# posture_corrector_schematic.net
KiCad netlist of a schematic drawn in Altium Designer
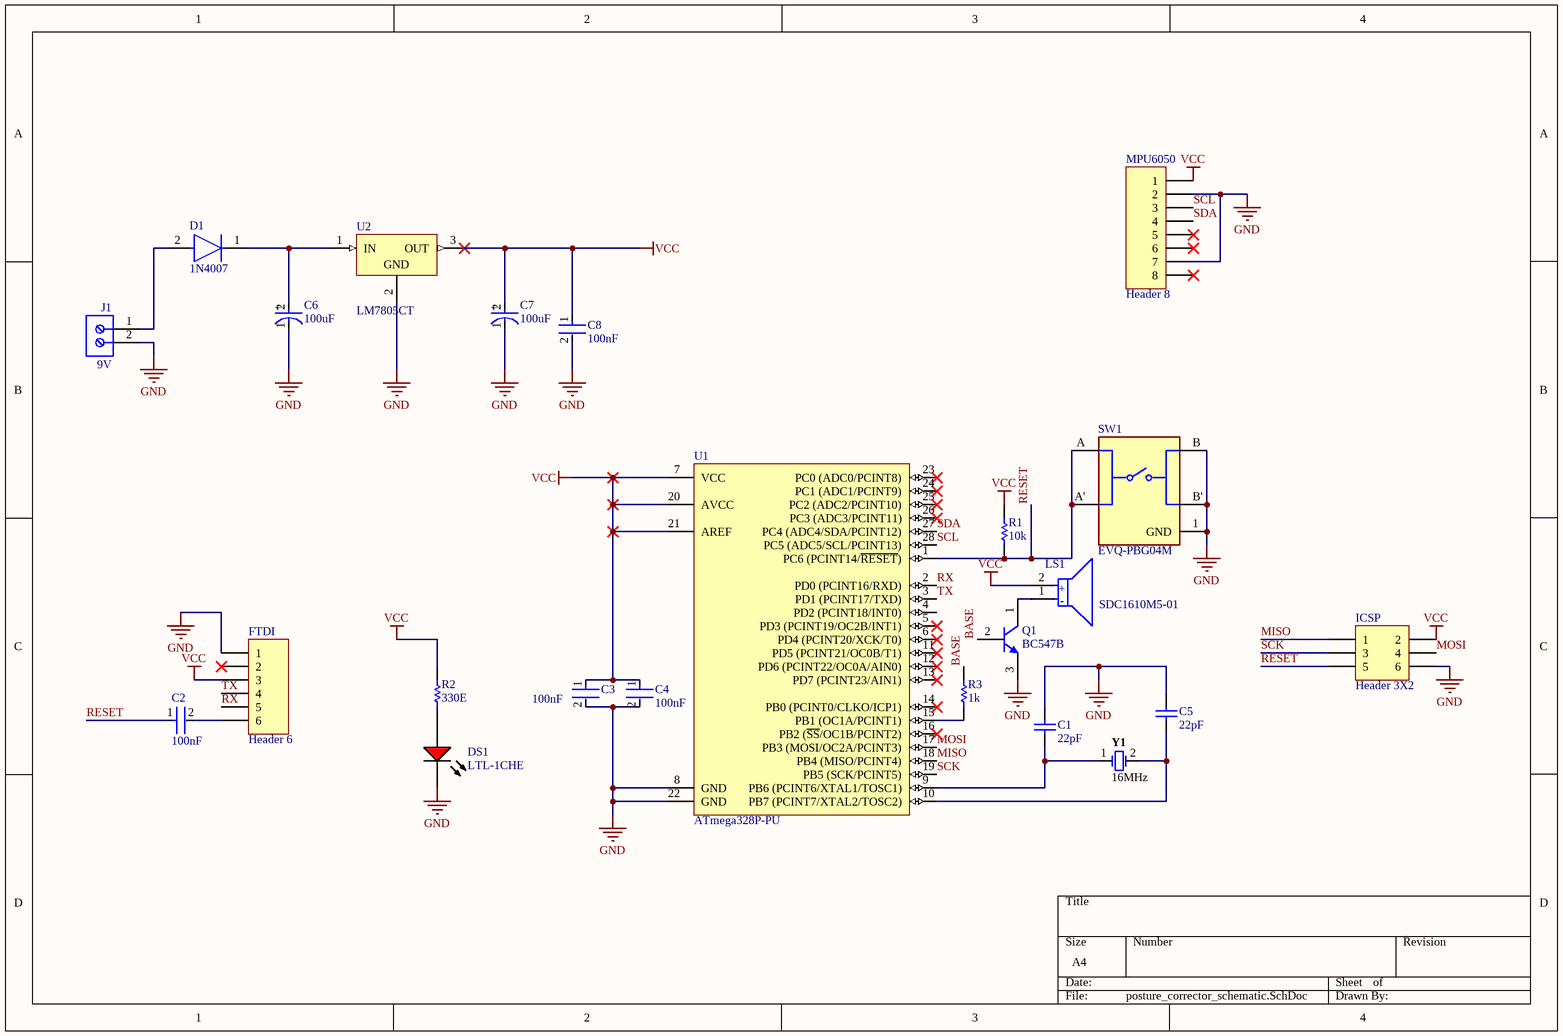
[diagram p0: posture_corrector_schematic.SchDoc]

(export (version "E")
  (design (tool "Eeschema 10.0.6"))
  (components
    (comp (ref "C1")
      (value "22pF")
      (footprint "KEMT-C315-THT-2")
      (description "Capacitor, Ceramic, 22 pF, +/-10 %, 100 V, -55 to 125 degC, 2-Pin THD, RoHS, Bulk")
      (libsource (lib "Altium Content Vault") (part "CAP-NP-2"))
    )
    (comp (ref "C2")
      (value "100nF")
      (footprint "FP-RCE1A2-MFG")
      (description "Cap Ceramic 100nF 100V X7R ±10% Radial 2.5mm +125°C Automotive Ammo Pack")
      (fields (field (name "TOLERANCE") "10%"))
      (libsource (lib "Altium Content Vault") (part "02cd4be3c70576c341d710602a673aa"))
    )
    (comp (ref "C3")
      (value "100nF")
      (footprint "FP-RCE1K1-2_5-MFG")
      (description "Cap Ceramic Monolithic 100nF 100V 10% Thru-Hole Bulk")
      (fields (field (name "TOLERANCE") "10%"))
      (libsource (lib "Altium Content Vault") (part "02cd4be3c70576c341d710602a673aa"))
    )
    (comp (ref "C4")
      (value "100nF")
      (footprint "FP-RCE1K1-2_5-MFG")
      (description "Cap Ceramic Monolithic 100nF 100V 10% Thru-Hole Bulk")
      (fields (field (name "TOLERANCE") "10%"))
      (libsource (lib "Altium Content Vault") (part "02cd4be3c70576c341d710602a673aa"))
    )
    (comp (ref "C5")
      (value "22pF")
      (footprint "KEMT-C315-THT-2")
      (description "Capacitor, Ceramic, 22 pF, +/-10 %, 100 V, -55 to 125 degC, 2-Pin THD, RoHS, Bulk")
      (libsource (lib "Altium Content Vault") (part "CAP-NP-2"))
    )
    (comp (ref "C6")
      (value "100uF")
      (footprint "FP-RAD-TH-D_6_3_0_5-L_11-MFG")
      (description "Aluminum Electrolytic Capacitors (Radial Lead Type) 2.2uF ±20% 250V")
      (fields (field (name "TOLERANCE") "20%"))
      (libsource (lib "Altium Content Vault") (part "203bc49f2ac43e59fd269a8c329ed05"))
    )
    (comp (ref "C7")
      (value "100uF")
      (footprint "FP-RAD-TH-D_6_3_0_5-L_11-MFG")
      (description "Aluminum Electrolytic Capacitors (Radial Lead Type) 2.2uF ±20% 250V")
      (fields (field (name "TOLERANCE") "20%"))
      (libsource (lib "Altium Content Vault") (part "203bc49f2ac43e59fd269a8c329ed05"))
    )
    (comp (ref "C8")
      (value "100nF")
      (footprint "FP-RCE1K1-2_5-MFG")
      (description "Cap Ceramic Monolithic 100nF 100V 10% Thru-Hole Bulk")
      (fields (field (name "TOLERANCE") "10%"))
      (libsource (lib "Altium Content Vault") (part "02cd4be3c70576c341d710602a673aa"))
    )
    (comp (ref "D1")
      (value "1N4007")
      (footprint "FP-1N4007E-E3-54-MFG")
      (description "DIODE GEN PURP 1KV 1A DO204AL")
      (libsource (lib "Altium Content Vault") (part "d7152d700b627762746794eb795d46e"))
    )
    (comp (ref "DS1")
      (value "LTL-1CHE")
      (footprint "INDPR60-254-520X380X650")
      (description "Radial LED, 12.6 mcd, 20 mA, 2 V, -55 to 100 degC, 2-Pin THD, RoHS, Bulk")
      (fields (field (name "TOLERANCE") "20%"))
      (libsource (lib "Altium Content Vault") (part "LED-RED-AK-2"))
    )
    (comp (ref "FTDI")
      (value "Header 6")
      (footprint "HDR1X6")
      (description "Header, 6-Pin")
      (fields (field (name "PUBLISHER") "Altium Limited"))
      (libsource (lib "Miscellaneous Connectors") (part "Header 6"))
    )
    (comp (ref "ICSP")
      (value "Header 3X2")
      (footprint "HDR2X3")
      (description "Header, 3-Pin, Dual row")
      (fields (field (name "PUBLISHER") "Altium Limited"))
      (libsource (lib "Miscellaneous Connectors") (part "Header 3X2"))
    )
    (comp (ref "J1")
      (value "9V")
      (footprint "691211720002")
      (description "211 Series 5MM Pitch Straight, Pcb Terminal Block, Through Hole, 2 Way")
      (fields (field (name "VOLTAGE") "300V"))
      (libsource (lib "Altium Content Vault") (part "TBL - 1R - 02P - Screw"))
    )
    (comp (ref "LS1")
      (value "SDC1610M5-01")
      (footprint "FP-SDC1610M5-01-MFG")
      (description "AUDIO MAGNETIC INDICATOR 4-8V TH")
      (libsource (lib "Altium Content Vault") (part "f7ec632b6fea80cbef86dc3340f200c"))
    )
    (comp (ref "MPU6050")
      (value "Header 8")
      (footprint "HDR1X8")
      (description "Header, 8-Pin")
      (fields (field (name "PUBLISHER") "Altium Limited"))
      (libsource (lib "Miscellaneous Connectors") (part "Header 8"))
    )
    (comp (ref "Q1")
      (value "BC547B")
      (footprint "ONSC-TO-92-3-29-11")
      (description "Amplifier Transistor, NPN Silicon, 3-Pin TO-92, Bulk Box")
      (fields (field (name "MANUFACTURER") "On Semiconductor"))
      (libsource (lib "Altium Content Vault") (part "ONSC-NPN-C1B2E3-3"))
    )
    (comp (ref "R1")
      (value "10k")
      (footprint "AXIAL-0.3")
      (description "Resistor")
      (fields (field (name "PUBLISHER") "Altium Limited"))
      (libsource (lib "Miscellaneous Devices") (part "Res1"))
    )
    (comp (ref "R2")
      (value "330E")
      (footprint "AXIAL-0.3")
      (description "Resistor")
      (fields (field (name "PUBLISHER") "Altium Limited"))
      (libsource (lib "Miscellaneous Devices") (part "Res1"))
    )
    (comp (ref "R3")
      (value "1k")
      (footprint "AXIAL-0.3")
      (description "Resistor")
      (fields (field (name "PUBLISHER") "Altium Limited"))
      (libsource (lib "Miscellaneous Devices") (part "Res1"))
    )
    (comp (ref "SW1")
      (value "EVQ-PBG04M")
      (footprint "FP-EVQ-PBG04M-MFG")
      (description "SWITCH TACTILE SPST-NO 0.02A 15V")
      (libsource (lib "Altium Content Vault") (part "2124b69ba03152b6ee5348f5a6e82e9"))
    )
    (comp (ref "U1")
      (value "ATmega328P-PU")
      (footprint "28P3")
      (libsource (lib "Altium Content Vault") (part "MC-8B-ATM48-IL28"))
    )
    (comp (ref "U2")
      (value "LM7805CT")
      (footprint "FAIR-TO-220-3")
      (description "Positive Voltage Regulator, 5 V, 1 A, -40 to 125 degC, 3-Pin TO-220, RoHS, Tube")
      (fields (field (name "MANUFACTURER") "FairchildSemiconductor"))
      (libsource (lib "Altium Content Vault") (part "FAIR-LM7805CT-TO220-3"))
    )
    (comp (ref "Y1")
      (value "16MHz")
      (footprint "FOX-FOXSLF160-20")
      (description "Resistance Weld Thru-Hole Crystal, 16 MHz, -20 to 70 degC, 2-Pin THD, RoHS, Bulk")
      (fields (field (name "TOLERANCE") "1%"))
      (libsource (lib "Altium Content Vault") (part "XTAL-1-2-2"))
    )
  )
  (nets
    (net (code "1") (name "/BASE") (class "Default")
      (node (ref "Q1") (pin "2") (pinfunction "B_2") (pintype "passive"))
      (node (ref "R3") (pin "2") (pinfunction "2_2") (pintype "passive"))
    )
    (net (code "2") (name "/MISO") (class "Default")
      (node (ref "ICSP") (pin "1") (pinfunction "1_1") (pintype "passive"))
      (node (ref "U1") (pin "18") (pinfunction "PB4_(MISO/PCINT4)_18") (pintype "bidirectional"))
    )
    (net (code "3") (name "/MOSI") (class "Default")
      (node (ref "ICSP") (pin "4") (pinfunction "4_4") (pintype "passive"))
      (node (ref "U1") (pin "17") (pinfunction "PB3_(MOSI/OC2A/PCINT3)_17") (pintype "bidirectional"))
    )
    (net (code "4") (name "/RESET") (class "Default")
      (node (ref "C2") (pin "1") (pinfunction "1_1") (pintype "passive"))
      (node (ref "ICSP") (pin "5") (pinfunction "5_5") (pintype "passive"))
      (node (ref "R1") (pin "1") (pinfunction "1_1") (pintype "passive"))
      (node (ref "SW1") (pin "A") (pinfunction "A_A") (pintype "passive"))
      (node (ref "SW1") (pin "A'") (pinfunction "A'_A'") (pintype "passive"))
      (node (ref "U1") (pin "1") (pinfunction "PC6_(PCINT14/~{RESET})_1") (pintype "bidirectional"))
    )
    (net (code "5") (name "/RX") (class "Default")
      (node (ref "FTDI") (pin "5") (pinfunction "5_5") (pintype "passive"))
      (node (ref "U1") (pin "2") (pinfunction "PD0_(PCINT16/RXD)_2") (pintype "bidirectional"))
    )
    (net (code "6") (name "/SCK") (class "Default")
      (node (ref "ICSP") (pin "3") (pinfunction "3_3") (pintype "passive"))
      (node (ref "U1") (pin "19") (pinfunction "PB5_(SCK/PCINT5)_19") (pintype "bidirectional"))
    )
    (net (code "7") (name "/SCL") (class "Default")
      (node (ref "MPU6050") (pin "3") (pinfunction "3_3") (pintype "passive"))
      (node (ref "U1") (pin "28") (pinfunction "PC5_(ADC5/SCL/PCINT13)_28") (pintype "bidirectional"))
    )
    (net (code "8") (name "/SDA") (class "Default")
      (node (ref "MPU6050") (pin "4") (pinfunction "4_4") (pintype "passive"))
      (node (ref "U1") (pin "27") (pinfunction "PC4_(ADC4/SDA/PCINT12)_27") (pintype "bidirectional"))
    )
    (net (code "9") (name "/TX") (class "Default")
      (node (ref "FTDI") (pin "4") (pinfunction "4_4") (pintype "passive"))
      (node (ref "U1") (pin "3") (pinfunction "PD1_(PCINT17/TXD)_3") (pintype "bidirectional"))
    )
    (net (code "10") (name "GND") (class "Default")
      (node (ref "C1") (pin "2") (pinfunction "2_2") (pintype "passive"))
      (node (ref "C3") (pin "2") (pinfunction "2_2") (pintype "passive"))
      (node (ref "C4") (pin "2") (pinfunction "2_2") (pintype "passive"))
      (node (ref "C5") (pin "2") (pinfunction "2_2") (pintype "passive"))
      (node (ref "C6") (pin "1") (pinfunction "C_1") (pintype "passive"))
      (node (ref "C7") (pin "1") (pinfunction "C_1") (pintype "passive"))
      (node (ref "C8") (pin "2") (pinfunction "2_2") (pintype "passive"))
      (node (ref "DS1") (pin "2") (pinfunction "K_2") (pintype "passive"))
      (node (ref "FTDI") (pin "1") (pinfunction "1_1") (pintype "passive"))
      (node (ref "ICSP") (pin "6") (pinfunction "6_6") (pintype "passive"))
      (node (ref "J1") (pin "2") (pinfunction "2_2") (pintype "passive"))
      (node (ref "MPU6050") (pin "2") (pinfunction "2_2") (pintype "passive"))
      (node (ref "MPU6050") (pin "7") (pinfunction "7_7") (pintype "passive"))
      (node (ref "Q1") (pin "3") (pinfunction "E_3") (pintype "passive"))
      (node (ref "SW1") (pin "1") (pinfunction "GND_1") (pintype "power_in"))
      (node (ref "SW1") (pin "B") (pinfunction "B_B") (pintype "passive"))
      (node (ref "SW1") (pin "B'") (pinfunction "B'_B'") (pintype "passive"))
      (node (ref "U1") (pin "22") (pinfunction "GND_22") (pintype "power_in"))
      (node (ref "U1") (pin "8") (pinfunction "GND_8") (pintype "power_in"))
      (node (ref "U2") (pin "2") (pinfunction "GND_2") (pintype "power_in"))
    )
    (net (code "11") (name "Net-(C2-Pad2)") (class "Default")
      (node (ref "C2") (pin "2") (pinfunction "2_2") (pintype "passive"))
      (node (ref "FTDI") (pin "6") (pinfunction "6_6") (pintype "passive"))
    )
    (net (code "12") (name "Net-(C6-A)") (class "Default")
      (node (ref "C6") (pin "2") (pinfunction "A_2") (pintype "passive"))
      (node (ref "D1") (pin "1") (pinfunction "C_1") (pintype "passive"))
      (node (ref "U2") (pin "1") (pinfunction "IN_1") (pintype "input"))
    )
    (net (code "13") (name "Net-(D1-A)") (class "Default")
      (node (ref "D1") (pin "2") (pinfunction "A_2") (pintype "passive"))
      (node (ref "J1") (pin "1") (pinfunction "1_1") (pintype "passive"))
    )
    (net (code "14") (name "Net-(DS1-A)") (class "Default")
      (node (ref "DS1") (pin "1") (pinfunction "A_1") (pintype "passive"))
      (node (ref "R2") (pin "1") (pinfunction "1_1") (pintype "passive"))
    )
    (net (code "15") (name "Net-(LS1-C)") (class "Default")
      (node (ref "LS1") (pin "1") (pinfunction "C_1") (pintype "passive"))
      (node (ref "Q1") (pin "1") (pinfunction "C_1") (pintype "passive"))
    )
    (net (code "16") (name "Net-(U1-PB1_(OC1A{slash}PCINT1))") (class "Default")
      (node (ref "R3") (pin "1") (pinfunction "1_1") (pintype "passive"))
      (node (ref "U1") (pin "15") (pinfunction "PB1_(OC1A/PCINT1)_15") (pintype "bidirectional"))
    )
    (net (code "17") (name "Net-(U1-PB6_(PCINT6{slash}XTAL1{slash}TOSC1))") (class "Default")
      (node (ref "C1") (pin "1") (pinfunction "1_1") (pintype "passive"))
      (node (ref "U1") (pin "9") (pinfunction "PB6_(PCINT6/XTAL1/TOSC1)_9") (pintype "bidirectional"))
      (node (ref "Y1") (pin "1") (pinfunction "1_1") (pintype "passive"))
    )
    (net (code "18") (name "Net-(U1-PB7_(PCINT7{slash}XTAL2{slash}TOSC2))") (class "Default")
      (node (ref "C5") (pin "1") (pinfunction "1_1") (pintype "passive"))
      (node (ref "U1") (pin "10") (pinfunction "PB7_(PCINT7/XTAL2/TOSC2)_10") (pintype "bidirectional"))
      (node (ref "Y1") (pin "2") (pinfunction "2_2") (pintype "passive"))
    )
    (net (code "19") (name "VCC") (class "Default")
      (node (ref "C3") (pin "1") (pinfunction "1_1") (pintype "passive"))
      (node (ref "C4") (pin "1") (pinfunction "1_1") (pintype "passive"))
      (node (ref "C7") (pin "2") (pinfunction "A_2") (pintype "passive"))
      (node (ref "C8") (pin "1") (pinfunction "1_1") (pintype "passive"))
      (node (ref "FTDI") (pin "3") (pinfunction "3_3") (pintype "passive"))
      (node (ref "ICSP") (pin "2") (pinfunction "2_2") (pintype "passive"))
      (node (ref "LS1") (pin "2") (pinfunction "A_2") (pintype "passive"))
      (node (ref "MPU6050") (pin "1") (pinfunction "1_1") (pintype "passive"))
      (node (ref "R1") (pin "2") (pinfunction "2_2") (pintype "passive"))
      (node (ref "R2") (pin "2") (pinfunction "2_2") (pintype "passive"))
      (node (ref "U1") (pin "20") (pinfunction "AVCC_20") (pintype "power_in"))
      (node (ref "U1") (pin "21") (pinfunction "AREF_21") (pintype "power_in"))
      (node (ref "U1") (pin "7") (pinfunction "VCC_7") (pintype "power_in"))
      (node (ref "U2") (pin "3") (pinfunction "OUT_3") (pintype "output"))
    )
    (net (code "20") (name "unconnected-(FTDI-Pad2)") (class "Default")
      (node (ref "FTDI") (pin "2") (pinfunction "2_2") (pintype "passive+no_connect"))
    )
    (net (code "21") (name "unconnected-(MPU6050-Pad5)") (class "Default")
      (node (ref "MPU6050") (pin "5") (pinfunction "5_5") (pintype "passive+no_connect"))
    )
    (net (code "22") (name "unconnected-(MPU6050-Pad6)") (class "Default")
      (node (ref "MPU6050") (pin "6") (pinfunction "6_6") (pintype "passive+no_connect"))
    )
    (net (code "23") (name "unconnected-(MPU6050-Pad8)") (class "Default")
      (node (ref "MPU6050") (pin "8") (pinfunction "8_8") (pintype "passive+no_connect"))
    )
    (net (code "24") (name "unconnected-(U1-PB0_(PCINT0{slash}CLKO{slash}ICP1)-Pad14)") (class "Default")
      (node (ref "U1") (pin "14") (pinfunction "PB0_(PCINT0/CLKO/ICP1)_14") (pintype "bidirectional+no_connect"))
    )
    (net (code "25") (name "unconnected-(U1-PB2_(~{SS}{slash}OC1B{slash}PCINT2)-Pad16)") (class "Default")
      (node (ref "U1") (pin "16") (pinfunction "PB2_(~{SS}/OC1B/PCINT2)_16") (pintype "bidirectional+no_connect"))
    )
    (net (code "26") (name "unconnected-(U1-PC0_(ADC0{slash}PCINT8)-Pad23)") (class "Default")
      (node (ref "U1") (pin "23") (pinfunction "PC0_(ADC0/PCINT8)_23") (pintype "bidirectional+no_connect"))
    )
    (net (code "27") (name "unconnected-(U1-PC1_(ADC1{slash}PCINT9)-Pad24)") (class "Default")
      (node (ref "U1") (pin "24") (pinfunction "PC1_(ADC1/PCINT9)_24") (pintype "bidirectional+no_connect"))
    )
    (net (code "28") (name "unconnected-(U1-PC2_(ADC2{slash}PCINT10)-Pad25)") (class "Default")
      (node (ref "U1") (pin "25") (pinfunction "PC2_(ADC2/PCINT10)_25") (pintype "bidirectional+no_connect"))
    )
    (net (code "29") (name "unconnected-(U1-PC3_(ADC3{slash}PCINT11)-Pad26)") (class "Default")
      (node (ref "U1") (pin "26") (pinfunction "PC3_(ADC3/PCINT11)_26") (pintype "bidirectional+no_connect"))
    )
    (net (code "30") (name "unconnected-(U1-PD2_(PCINT18{slash}INT0)-Pad4)") (class "Default")
      (node (ref "U1") (pin "4") (pinfunction "PD2_(PCINT18/INT0)_4") (pintype "bidirectional"))
    )
    (net (code "31") (name "unconnected-(U1-PD3_(PCINT19{slash}OC2B{slash}INT1)-Pad5)") (class "Default")
      (node (ref "U1") (pin "5") (pinfunction "PD3_(PCINT19/OC2B/INT1)_5") (pintype "bidirectional+no_connect"))
    )
    (net (code "32") (name "unconnected-(U1-PD4_(PCINT20{slash}XCK{slash}T0)-Pad6)") (class "Default")
      (node (ref "U1") (pin "6") (pinfunction "PD4_(PCINT20/XCK/T0)_6") (pintype "bidirectional+no_connect"))
    )
    (net (code "33") (name "unconnected-(U1-PD5_(PCINT21{slash}OC0B{slash}T1)-Pad11)") (class "Default")
      (node (ref "U1") (pin "11") (pinfunction "PD5_(PCINT21/OC0B/T1)_11") (pintype "bidirectional+no_connect"))
    )
    (net (code "34") (name "unconnected-(U1-PD6_(PCINT22{slash}OC0A{slash}AIN0)-Pad12)") (class "Default")
      (node (ref "U1") (pin "12") (pinfunction "PD6_(PCINT22/OC0A/AIN0)_12") (pintype "bidirectional+no_connect"))
    )
    (net (code "35") (name "unconnected-(U1-PD7_(PCINT23{slash}AIN1)-Pad13)") (class "Default")
      (node (ref "U1") (pin "13") (pinfunction "PD7_(PCINT23/AIN1)_13") (pintype "bidirectional+no_connect"))
    )
  )
)
